# Controller.net
KiCad netlist of a schematic drawn in EAGLE
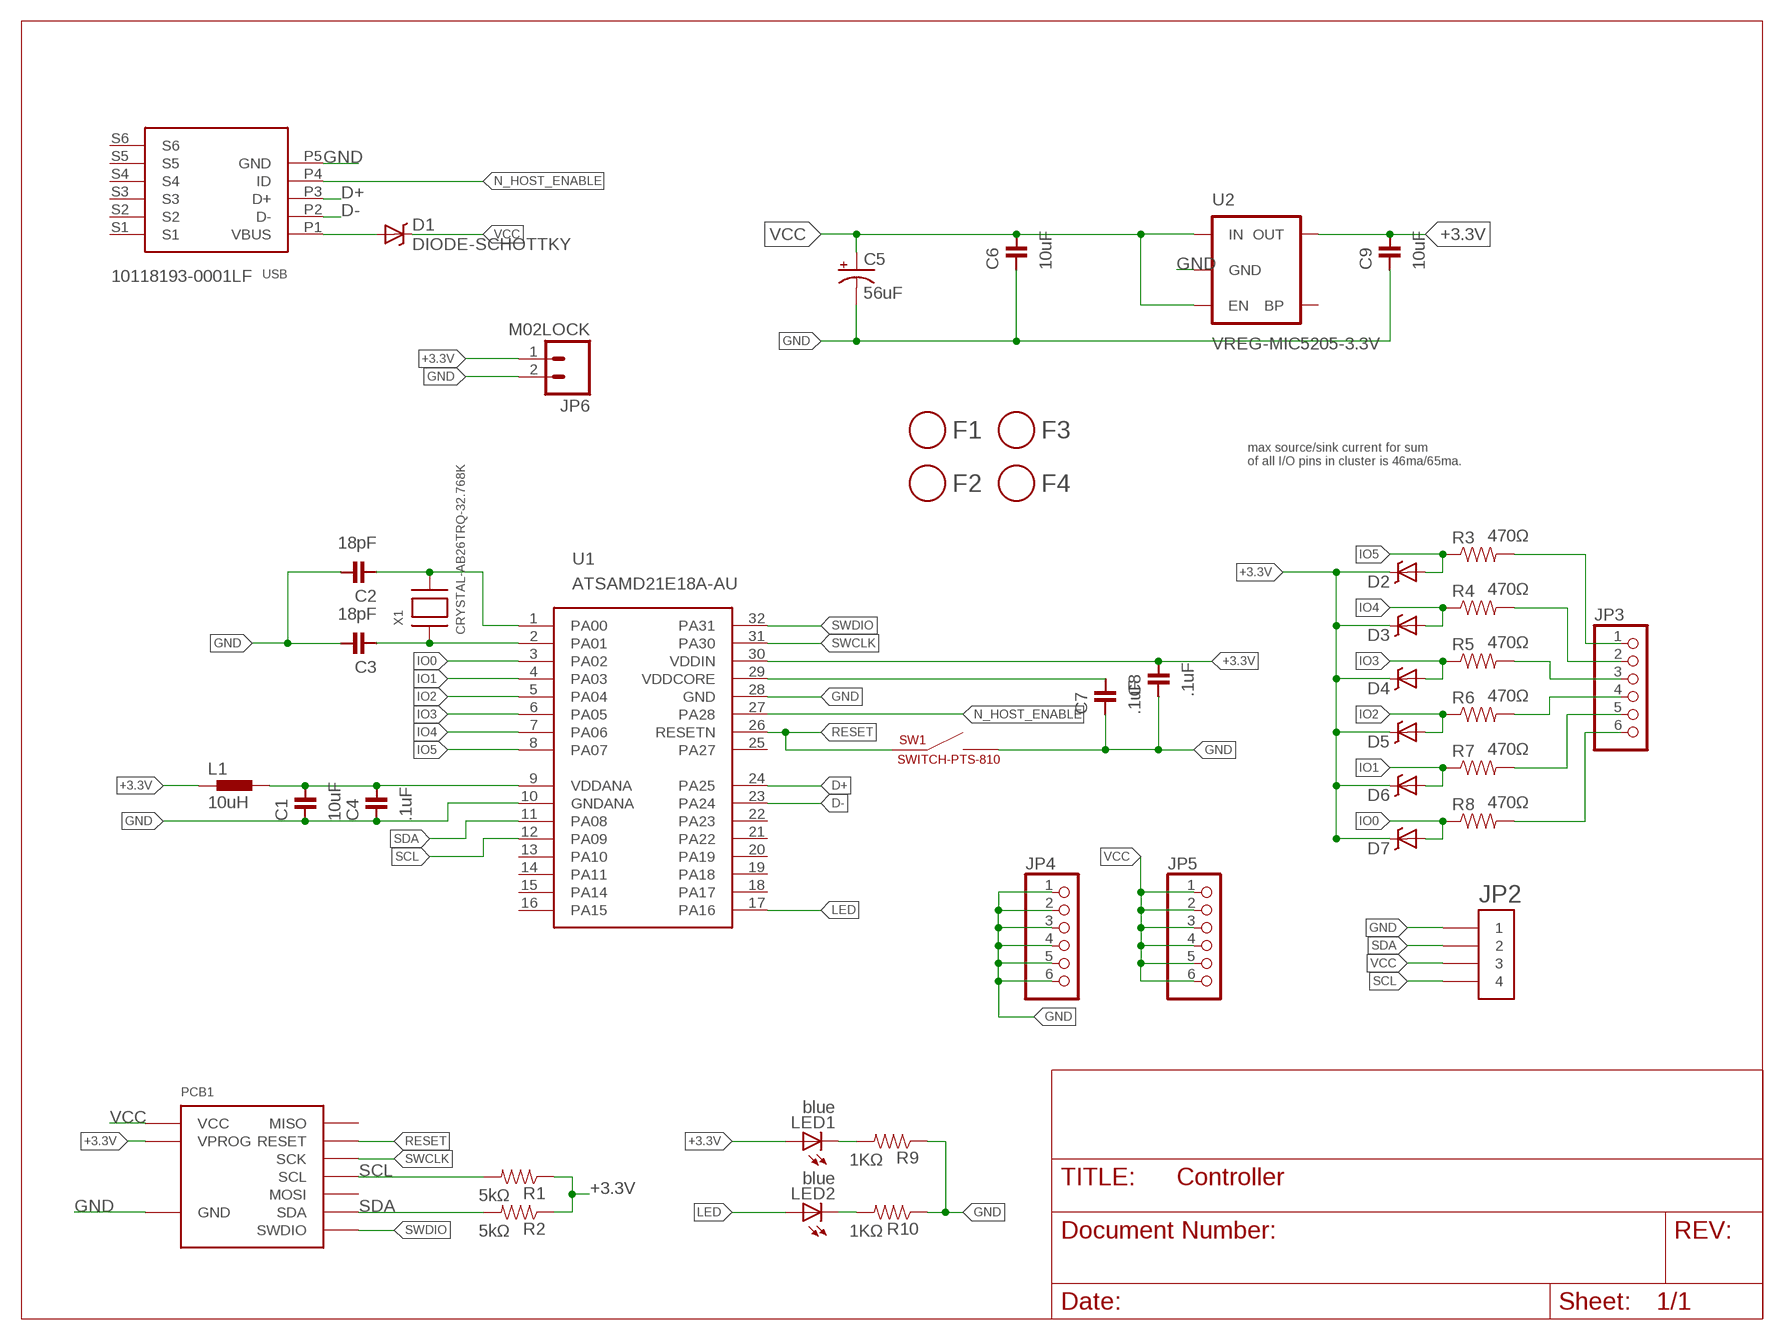
[diagram p0: schematic, sheet 1]

(export (version "E")
  (design (tool "Eeschema 10.0.6"))
  (components
    (comp (ref "C1")
      (value "10uF")
      (footprint "eagle-import:0603")
      (fields (field (name "PARTNUM") "GRM188R61C106MA73D"))
      (libsource (lib "eagle-import") (part "CAPACITOR-10UF"))
    )
    (comp (ref "C2")
      (value "18pF")
      (footprint "eagle-import:0603")
      (fields (field (name "PARTNUM") "C0603C180J5GACTU"))
      (libsource (lib "eagle-import") (part "CAPACITOR-18PF"))
    )
    (comp (ref "C3")
      (value "18pF")
      (footprint "eagle-import:0603")
      (fields (field (name "PARTNUM") "C0603C180J5GACTU"))
      (libsource (lib "eagle-import") (part "CAPACITOR-18PF"))
    )
    (comp (ref "C4")
      (value ".1uF")
      (footprint "eagle-import:0603")
      (fields (field (name "PARTNUM") "C0603C104K5RACTU"))
      (libsource (lib "eagle-import") (part "CAPACITOR-.1UF"))
    )
    (comp (ref "C5")
      (value "56uF")
      (footprint "eagle-import:PANASONIC_D")
      (fields (field (name "PARTNUM") "EMVA250ADA560MF55G"))
      (libsource (lib "eagle-import") (part "CAPACITOR-POL-56UF-25V"))
    )
    (comp (ref "C6")
      (value "10uF")
      (footprint "eagle-import:0603")
      (fields (field (name "PARTNUM") "GRM188R61C106MA73D"))
      (libsource (lib "eagle-import") (part "CAPACITOR-10UF"))
    )
    (comp (ref "C7")
      (value ".1uF")
      (footprint "eagle-import:0603")
      (fields (field (name "PARTNUM") "C0603C104K5RACTU"))
      (libsource (lib "eagle-import") (part "CAPACITOR-.1UF"))
    )
    (comp (ref "C8")
      (value ".1uF")
      (footprint "eagle-import:0603")
      (fields (field (name "PARTNUM") "C0603C104K5RACTU"))
      (libsource (lib "eagle-import") (part "CAPACITOR-.1UF"))
    )
    (comp (ref "C9")
      (value "10uF")
      (footprint "eagle-import:0603")
      (fields (field (name "PARTNUM") "GRM188R61C106MA73D"))
      (libsource (lib "eagle-import") (part "CAPACITOR-10UF"))
    )
    (comp (ref "D1")
      (value "DIODE-SCHOTTKY")
      (footprint "eagle-import:SMP")
      (fields (field (name "PARTNUM") "SS3P3-M3/84A"))
      (libsource (lib "eagle-import") (part "DIODE-SCHOTTKY"))
    )
    (comp (ref "D2")
      (value "DIODE-SCHOTTKY-BAT60A")
      (footprint "eagle-import:SOD-323")
      (fields (field (name "PARTNUM") "BAT60A") (field (name "PARTNUM_1") "RB751V40"))
      (libsource (lib "eagle-import") (part "DIODE-SCHOTTKY-BAT60A"))
    )
    (comp (ref "D3")
      (value "DIODE-SCHOTTKY-BAT60A")
      (footprint "eagle-import:SOD-323")
      (fields (field (name "PARTNUM") "BAT60A") (field (name "PARTNUM_1") "RB751V40"))
      (libsource (lib "eagle-import") (part "DIODE-SCHOTTKY-BAT60A"))
    )
    (comp (ref "D4")
      (value "DIODE-SCHOTTKY-BAT60A")
      (footprint "eagle-import:SOD-323")
      (fields (field (name "PARTNUM") "BAT60A") (field (name "PARTNUM_1") "RB751V40"))
      (libsource (lib "eagle-import") (part "DIODE-SCHOTTKY-BAT60A"))
    )
    (comp (ref "D5")
      (value "DIODE-SCHOTTKY-BAT60A")
      (footprint "eagle-import:SOD-323")
      (fields (field (name "PARTNUM") "BAT60A") (field (name "PARTNUM_1") "RB751V40"))
      (libsource (lib "eagle-import") (part "DIODE-SCHOTTKY-BAT60A"))
    )
    (comp (ref "D6")
      (value "DIODE-SCHOTTKY-BAT60A")
      (footprint "eagle-import:SOD-323")
      (fields (field (name "PARTNUM") "BAT60A") (field (name "PARTNUM_1") "RB751V40"))
      (libsource (lib "eagle-import") (part "DIODE-SCHOTTKY-BAT60A"))
    )
    (comp (ref "D7")
      (value "DIODE-SCHOTTKY-BAT60A")
      (footprint "eagle-import:SOD-323")
      (fields (field (name "PARTNUM") "BAT60A") (field (name "PARTNUM_1") "RB751V40"))
      (libsource (lib "eagle-import") (part "DIODE-SCHOTTKY-BAT60A"))
    )
    (comp (ref "F1")
      (value "FIDUCIAL")
      (footprint "eagle-import:FIDUCIAL_1MM")
      (libsource (lib "eagle-import") (part "FIDUCIAL"))
    )
    (comp (ref "F2")
      (value "FIDUCIAL")
      (footprint "eagle-import:FIDUCIAL_1MM")
      (libsource (lib "eagle-import") (part "FIDUCIAL"))
    )
    (comp (ref "F3")
      (value "FIDUCIAL")
      (footprint "eagle-import:FIDUCIAL_1MM")
      (libsource (lib "eagle-import") (part "FIDUCIAL"))
    )
    (comp (ref "F4")
      (value "FIDUCIAL")
      (footprint "eagle-import:FIDUCIAL_1MM")
      (libsource (lib "eagle-import") (part "FIDUCIAL"))
    )
    (comp (ref "JP1")
      (value "USBFCI-MICROB")
      (footprint "eagle-import:USB-MICROB-FCI")
      (fields (field (name "PARTNUM") "10118193-0001LF"))
      (libsource (lib "eagle-import") (part "USBFCI-MICROB"))
    )
    (comp (ref "JP2")
      (value "HEADER-1X4-AMPMODU")
      (footprint "eagle-import:AMPMODU-4P")
      (fields (field (name "PARTNUM") "147721-3"))
      (libsource (lib "eagle-import") (part "HEADER-1X4-AMPMODU"))
    )
    (comp (ref "JP3")
      (value "PINHD-1X6LOCK")
      (footprint "eagle-import:1X06-BIGLOCK")
      (fields (field (name "PARTNUM") "M20-9990646"))
      (libsource (lib "eagle-import") (part "PINHD-1X6LOCK"))
    )
    (comp (ref "JP4")
      (value "PINHD-1X6LOCK")
      (footprint "eagle-import:1X06-BIGLOCK")
      (fields (field (name "PARTNUM") "M20-9990646"))
      (libsource (lib "eagle-import") (part "PINHD-1X6LOCK"))
    )
    (comp (ref "JP5")
      (value "PINHD-1X6LOCK")
      (footprint "eagle-import:1X06-BIGLOCK")
      (fields (field (name "PARTNUM") "M20-9990646"))
      (libsource (lib "eagle-import") (part "PINHD-1X6LOCK"))
    )
    (comp (ref "JP6")
      (value "M02LOCK")
      (footprint "eagle-import:1X02_LOCK")
      (fields (field (name "PARTNUM") "M20-9990246"))
      (libsource (lib "eagle-import") (part "M02LOCK"))
    )
    (comp (ref "L1")
      (value "10uH")
      (footprint "eagle-import:0603")
      (fields (field (name "PARTNUM") "LQM18FN100M00D") (field (name "PARTNUM_1") "BLM18TG102TN1D"))
      (libsource (lib "eagle-import") (part "INDUCTOR-10UH"))
    )
    (comp (ref "LED1")
      (value "blue")
      (footprint "eagle-import:0805-LED")
      (fields (field (name "PARTNUM") "LTST-C171TBKT") (field (name "PARTNUM_1") "LTST-C171KRKT"))
      (libsource (lib "eagle-import") (part "LED-0805-BLUE"))
    )
    (comp (ref "LED2")
      (value "blue")
      (footprint "eagle-import:0805-LED")
      (fields (field (name "PARTNUM") "LTST-C171TBKT"))
      (libsource (lib "eagle-import") (part "LED-0805-BLUE"))
    )
    (comp (ref "PCB1")
      (value "DEVICE-PCB")
      (footprint "eagle-import:DEVICE-PCB")
      (fields (field (name "PARTNUM") "Controller PCB"))
      (libsource (lib "eagle-import") (part "DEVICE-PCB"))
    )
    (comp (ref "R1")
      (value "5kΩ")
      (footprint "eagle-import:0603")
      (fields (field (name "PARTNUM") "ERJ-3EKF5101V"))
      (libsource (lib "eagle-import") (part "RESISTOR-5KΩ"))
    )
    (comp (ref "R2")
      (value "5kΩ")
      (footprint "eagle-import:0603")
      (fields (field (name "PARTNUM") "ERJ-3EKF5101V"))
      (libsource (lib "eagle-import") (part "RESISTOR-5KΩ"))
    )
    (comp (ref "R3")
      (value "470Ω")
      (footprint "eagle-import:0603")
      (fields (field (name "PARTNUM") "ERJ-3EKF4700V"))
      (libsource (lib "eagle-import") (part "RESISTOR-470Ω"))
    )
    (comp (ref "R4")
      (value "470Ω")
      (footprint "eagle-import:0603")
      (fields (field (name "PARTNUM") "ERJ-3EKF4700V"))
      (libsource (lib "eagle-import") (part "RESISTOR-470Ω"))
    )
    (comp (ref "R5")
      (value "470Ω")
      (footprint "eagle-import:0603")
      (fields (field (name "PARTNUM") "ERJ-3EKF4700V"))
      (libsource (lib "eagle-import") (part "RESISTOR-470Ω"))
    )
    (comp (ref "R6")
      (value "470Ω")
      (footprint "eagle-import:0603")
      (fields (field (name "PARTNUM") "ERJ-3EKF4700V"))
      (libsource (lib "eagle-import") (part "RESISTOR-470Ω"))
    )
    (comp (ref "R7")
      (value "470Ω")
      (footprint "eagle-import:0603")
      (fields (field (name "PARTNUM") "ERJ-3EKF4700V"))
      (libsource (lib "eagle-import") (part "RESISTOR-470Ω"))
    )
    (comp (ref "R8")
      (value "470Ω")
      (footprint "eagle-import:0603")
      (fields (field (name "PARTNUM") "ERJ-3EKF4700V"))
      (libsource (lib "eagle-import") (part "RESISTOR-470Ω"))
    )
    (comp (ref "R9")
      (value "1KΩ")
      (footprint "eagle-import:0603")
      (fields (field (name "PARTNUM") "ERJ-3EKF1001V"))
      (libsource (lib "eagle-import") (part "RESISTOR-1KΩ"))
    )
    (comp (ref "R10")
      (value "1KΩ")
      (footprint "eagle-import:0603")
      (fields (field (name "PARTNUM") "ERJ-3EKF1001V"))
      (libsource (lib "eagle-import") (part "RESISTOR-1KΩ"))
    )
    (comp (ref "SW1")
      (value "SWITCH-PTS-810")
      (footprint "eagle-import:TACT-SWITCH-PTS-810")
      (fields (field (name "PARTNUM") "PTS810 SJM 250 SMTR LFS"))
      (libsource (lib "eagle-import") (part "SWITCH-PTS-810"))
    )
    (comp (ref "U1")
      (value "ATSAMD21E18A-AU")
      (footprint "eagle-import:TQFP-32")
      (fields (field (name "PARTNUM") "ATSAMD21E18A-AUT"))
      (libsource (lib "eagle-import") (part "SAMD21E"))
    )
    (comp (ref "U2")
      (value "VREG-MIC5205-3.3V")
      (footprint "eagle-import:SOT23-5")
      (fields (field (name "PARTNUM") "MIC5205-3.3YM5 TR") (field (name "PARTNUM_1") "MIC5205-3.3YM5 TR"))
      (libsource (lib "eagle-import") (part "VREG-MIC5205-3.3V"))
    )
    (comp (ref "X1")
      (value "CRYSTAL-AB26TRQ-32.768K")
      (footprint "eagle-import:CRYSTAL-AB26TRQ")
      (fields (field (name "PARTNUM") "AB26TRQ-32.768KHZ-T"))
      (libsource (lib "eagle-import") (part "CRYSTAL-AB26TRQ-32.768K"))
    )
  )
  (nets
    (net (code "1") (name "+3.3V") (class "Default")
      (node (ref "C8") (pin "1") (pinfunction "1_1") (pintype "passive"))
      (node (ref "C9") (pin "1") (pinfunction "1_1") (pintype "passive"))
      (node (ref "D2") (pin "C") (pinfunction "C_C") (pintype "passive"))
      (node (ref "D3") (pin "C") (pinfunction "C_C") (pintype "passive"))
      (node (ref "D4") (pin "C") (pinfunction "C_C") (pintype "passive"))
      (node (ref "D5") (pin "C") (pinfunction "C_C") (pintype "passive"))
      (node (ref "D6") (pin "C") (pinfunction "C_C") (pintype "passive"))
      (node (ref "D7") (pin "C") (pinfunction "C_C") (pintype "passive"))
      (node (ref "JP6") (pin "1") (pinfunction "1_1") (pintype "passive"))
      (node (ref "L1") (pin "1") (pinfunction "1_1") (pintype "passive"))
      (node (ref "LED1") (pin "A") (pinfunction "A_A") (pintype "passive"))
      (node (ref "PCB1") (pin "VPROG") (pinfunction "VPROG_VPROG") (pintype "bidirectional"))
      (node (ref "R1") (pin "1") (pinfunction "1_1") (pintype "passive"))
      (node (ref "R2") (pin "1") (pinfunction "1_1") (pintype "passive"))
      (node (ref "U1") (pin "30") (pinfunction "VDDIN_30") (pintype "bidirectional"))
      (node (ref "U2") (pin "5") (pinfunction "OUT_5") (pintype "passive"))
    )
    (net (code "2") (name "D+") (class "Default")
      (node (ref "JP1") (pin "P3") (pinfunction "D+_P3") (pintype "bidirectional"))
      (node (ref "U1") (pin "24") (pinfunction "PA25_24") (pintype "bidirectional"))
    )
    (net (code "3") (name "D-") (class "Default")
      (node (ref "JP1") (pin "P2") (pinfunction "D-_P2") (pintype "bidirectional"))
      (node (ref "U1") (pin "23") (pinfunction "PA24_23") (pintype "bidirectional"))
    )
    (net (code "4") (name "GND") (class "Default")
      (node (ref "C1") (pin "2") (pinfunction "2_2") (pintype "passive"))
      (node (ref "C2") (pin "1") (pinfunction "1_1") (pintype "passive"))
      (node (ref "C3") (pin "1") (pinfunction "1_1") (pintype "passive"))
      (node (ref "C4") (pin "2") (pinfunction "2_2") (pintype "passive"))
      (node (ref "C5") (pin "-") (pinfunction "-_-") (pintype "passive"))
      (node (ref "C6") (pin "2") (pinfunction "2_2") (pintype "passive"))
      (node (ref "C7") (pin "2") (pinfunction "2_2") (pintype "passive"))
      (node (ref "C8") (pin "2") (pinfunction "2_2") (pintype "passive"))
      (node (ref "C9") (pin "2") (pinfunction "2_2") (pintype "passive"))
      (node (ref "JP1") (pin "P5") (pinfunction "GND_P5") (pintype "bidirectional"))
      (node (ref "JP2") (pin "P$1") (pinfunction "1_P$1") (pintype "bidirectional"))
      (node (ref "JP2") (pin "P$2") (pinfunction "1_P$2") (pintype "bidirectional"))
      (node (ref "JP4") (pin "1") (pinfunction "1_1") (pintype "passive"))
      (node (ref "JP4") (pin "2") (pinfunction "2_2") (pintype "passive"))
      (node (ref "JP4") (pin "3") (pinfunction "3_3") (pintype "passive"))
      (node (ref "JP4") (pin "4") (pinfunction "4_4") (pintype "passive"))
      (node (ref "JP4") (pin "5") (pinfunction "5_5") (pintype "passive"))
      (node (ref "JP4") (pin "6") (pinfunction "6_6") (pintype "passive"))
      (node (ref "JP6") (pin "2") (pinfunction "2_2") (pintype "passive"))
      (node (ref "PCB1") (pin "GND") (pinfunction "GND_GND") (pintype "bidirectional"))
      (node (ref "R10") (pin "1") (pinfunction "1_1") (pintype "passive"))
      (node (ref "R9") (pin "1") (pinfunction "1_1") (pintype "passive"))
      (node (ref "SW1") (pin "P$3") (pinfunction "NEG1_P$3") (pintype "bidirectional"))
      (node (ref "SW1") (pin "P$4") (pinfunction "NEG1_P$4") (pintype "bidirectional"))
      (node (ref "U1") (pin "10") (pinfunction "GNDANA_10") (pintype "bidirectional"))
      (node (ref "U1") (pin "28") (pinfunction "GND_28") (pintype "bidirectional"))
      (node (ref "U2") (pin "2") (pinfunction "GND_2") (pintype "input"))
    )
    (net (code "5") (name "IO0") (class "Default")
      (node (ref "D7") (pin "A") (pinfunction "A_A") (pintype "passive"))
      (node (ref "R8") (pin "1") (pinfunction "1_1") (pintype "passive"))
      (node (ref "U1") (pin "3") (pinfunction "PA02_3") (pintype "bidirectional"))
    )
    (net (code "6") (name "IO1") (class "Default")
      (node (ref "D6") (pin "A") (pinfunction "A_A") (pintype "passive"))
      (node (ref "R7") (pin "1") (pinfunction "1_1") (pintype "passive"))
      (node (ref "U1") (pin "4") (pinfunction "PA03_4") (pintype "bidirectional"))
    )
    (net (code "7") (name "IO2") (class "Default")
      (node (ref "D5") (pin "A") (pinfunction "A_A") (pintype "passive"))
      (node (ref "R6") (pin "1") (pinfunction "1_1") (pintype "passive"))
      (node (ref "U1") (pin "5") (pinfunction "PA04_5") (pintype "bidirectional"))
    )
    (net (code "8") (name "IO3") (class "Default")
      (node (ref "D4") (pin "A") (pinfunction "A_A") (pintype "passive"))
      (node (ref "R5") (pin "1") (pinfunction "1_1") (pintype "passive"))
      (node (ref "U1") (pin "6") (pinfunction "PA05_6") (pintype "bidirectional"))
    )
    (net (code "9") (name "IO4") (class "Default")
      (node (ref "D3") (pin "A") (pinfunction "A_A") (pintype "passive"))
      (node (ref "R4") (pin "1") (pinfunction "1_1") (pintype "passive"))
      (node (ref "U1") (pin "7") (pinfunction "PA06_7") (pintype "bidirectional"))
    )
    (net (code "10") (name "IO5") (class "Default")
      (node (ref "D2") (pin "A") (pinfunction "A_A") (pintype "passive"))
      (node (ref "R3") (pin "1") (pinfunction "1_1") (pintype "passive"))
      (node (ref "U1") (pin "8") (pinfunction "PA07_8") (pintype "bidirectional"))
    )
    (net (code "11") (name "LED") (class "Default")
      (node (ref "LED2") (pin "A") (pinfunction "A_A") (pintype "passive"))
      (node (ref "U1") (pin "17") (pinfunction "PA16_17") (pintype "bidirectional"))
    )
    (net (code "12") (name "N_HOST_ENABLE") (class "Default")
      (node (ref "JP1") (pin "P4") (pinfunction "ID_P4") (pintype "bidirectional"))
      (node (ref "U1") (pin "27") (pinfunction "PA28_27") (pintype "bidirectional"))
    )
    (net (code "13") (name "Net-(JP1-VBUS)") (class "Default")
      (node (ref "D1") (pin "A") (pinfunction "A_A") (pintype "passive"))
      (node (ref "JP1") (pin "P1") (pinfunction "VBUS_P1") (pintype "bidirectional"))
    )
    (net (code "14") (name "Net-(JP3-Pad1)") (class "Default")
      (node (ref "JP3") (pin "1") (pinfunction "1_1") (pintype "passive"))
      (node (ref "R3") (pin "2") (pinfunction "2_2") (pintype "passive"))
    )
    (net (code "15") (name "Net-(JP3-Pad2)") (class "Default")
      (node (ref "JP3") (pin "2") (pinfunction "2_2") (pintype "passive"))
      (node (ref "R4") (pin "2") (pinfunction "2_2") (pintype "passive"))
    )
    (net (code "16") (name "Net-(JP3-Pad3)") (class "Default")
      (node (ref "JP3") (pin "3") (pinfunction "3_3") (pintype "passive"))
      (node (ref "R5") (pin "2") (pinfunction "2_2") (pintype "passive"))
    )
    (net (code "17") (name "Net-(JP3-Pad4)") (class "Default")
      (node (ref "JP3") (pin "4") (pinfunction "4_4") (pintype "passive"))
      (node (ref "R6") (pin "2") (pinfunction "2_2") (pintype "passive"))
    )
    (net (code "18") (name "Net-(JP3-Pad5)") (class "Default")
      (node (ref "JP3") (pin "5") (pinfunction "5_5") (pintype "passive"))
      (node (ref "R7") (pin "2") (pinfunction "2_2") (pintype "passive"))
    )
    (net (code "19") (name "Net-(JP3-Pad6)") (class "Default")
      (node (ref "JP3") (pin "6") (pinfunction "6_6") (pintype "passive"))
      (node (ref "R8") (pin "2") (pinfunction "2_2") (pintype "passive"))
    )
    (net (code "20") (name "Net-(LED1-PadC)") (class "Default")
      (node (ref "LED1") (pin "C") (pinfunction "C_C") (pintype "passive"))
      (node (ref "R9") (pin "2") (pinfunction "2_2") (pintype "passive"))
    )
    (net (code "21") (name "Net-(LED2-PadC)") (class "Default")
      (node (ref "LED2") (pin "C") (pinfunction "C_C") (pintype "passive"))
      (node (ref "R10") (pin "2") (pinfunction "2_2") (pintype "passive"))
    )
    (net (code "22") (name "Net-(U1-PA00)") (class "Default")
      (node (ref "C2") (pin "2") (pinfunction "2_2") (pintype "passive"))
      (node (ref "U1") (pin "1") (pinfunction "PA00_1") (pintype "bidirectional"))
      (node (ref "X1") (pin "XOUT") (pinfunction "X2_XOUT") (pintype "bidirectional"))
    )
    (net (code "23") (name "Net-(U1-PA01)") (class "Default")
      (node (ref "C3") (pin "2") (pinfunction "2_2") (pintype "passive"))
      (node (ref "U1") (pin "2") (pinfunction "PA01_2") (pintype "bidirectional"))
      (node (ref "X1") (pin "XIN") (pinfunction "X1_XIN") (pintype "bidirectional"))
    )
    (net (code "24") (name "Net-(U1-VDDANA)") (class "Default")
      (node (ref "C1") (pin "1") (pinfunction "1_1") (pintype "passive"))
      (node (ref "C4") (pin "1") (pinfunction "1_1") (pintype "passive"))
      (node (ref "L1") (pin "2") (pinfunction "2_2") (pintype "passive"))
      (node (ref "U1") (pin "9") (pinfunction "VDDANA_9") (pintype "bidirectional"))
    )
    (net (code "25") (name "Net-(U1-VDDCORE)") (class "Default")
      (node (ref "C7") (pin "1") (pinfunction "1_1") (pintype "passive"))
      (node (ref "U1") (pin "29") (pinfunction "VDDCORE_29") (pintype "bidirectional"))
    )
    (net (code "26") (name "RESET") (class "Default")
      (node (ref "PCB1") (pin "RESET") (pinfunction "RESET_RESET") (pintype "bidirectional"))
      (node (ref "SW1") (pin "P$1") (pinfunction "POS1_P$1") (pintype "bidirectional"))
      (node (ref "SW1") (pin "P$2") (pinfunction "POS1_P$2") (pintype "bidirectional"))
      (node (ref "U1") (pin "26") (pinfunction "RESETN_26") (pintype "bidirectional"))
    )
    (net (code "27") (name "SCL") (class "Default")
      (node (ref "JP2") (pin "P$7") (pinfunction "4_P$7") (pintype "bidirectional"))
      (node (ref "JP2") (pin "P$8") (pinfunction "4_P$8") (pintype "bidirectional"))
      (node (ref "PCB1") (pin "SCL") (pinfunction "SCL_SCL") (pintype "bidirectional"))
      (node (ref "R1") (pin "2") (pinfunction "2_2") (pintype "passive"))
      (node (ref "U1") (pin "12") (pinfunction "PA09_12") (pintype "bidirectional"))
    )
    (net (code "28") (name "SDA") (class "Default")
      (node (ref "JP2") (pin "P$3") (pinfunction "2_P$3") (pintype "bidirectional"))
      (node (ref "JP2") (pin "P$4") (pinfunction "2_P$4") (pintype "bidirectional"))
      (node (ref "PCB1") (pin "SDA") (pinfunction "SDA_SDA") (pintype "bidirectional"))
      (node (ref "R2") (pin "2") (pinfunction "2_2") (pintype "passive"))
      (node (ref "U1") (pin "11") (pinfunction "PA08_11") (pintype "bidirectional"))
    )
    (net (code "29") (name "SWCLK") (class "Default")
      (node (ref "PCB1") (pin "CLK") (pinfunction "SCK_CLK") (pintype "bidirectional"))
      (node (ref "U1") (pin "31") (pinfunction "PA30_31") (pintype "bidirectional"))
    )
    (net (code "30") (name "SWDIO") (class "Default")
      (node (ref "PCB1") (pin "SWDIO") (pinfunction "SWDIO_SWDIO") (pintype "bidirectional"))
      (node (ref "U1") (pin "32") (pinfunction "PA31_32") (pintype "bidirectional"))
    )
    (net (code "31") (name "VCC") (class "Default")
      (node (ref "C5") (pin "+") (pinfunction "+_+") (pintype "passive"))
      (node (ref "C6") (pin "1") (pinfunction "1_1") (pintype "passive"))
      (node (ref "D1") (pin "C") (pinfunction "C_C") (pintype "passive"))
      (node (ref "JP2") (pin "P$5") (pinfunction "3_P$5") (pintype "bidirectional"))
      (node (ref "JP2") (pin "P$6") (pinfunction "3_P$6") (pintype "bidirectional"))
      (node (ref "JP5") (pin "1") (pinfunction "1_1") (pintype "passive"))
      (node (ref "JP5") (pin "2") (pinfunction "2_2") (pintype "passive"))
      (node (ref "JP5") (pin "3") (pinfunction "3_3") (pintype "passive"))
      (node (ref "JP5") (pin "4") (pinfunction "4_4") (pintype "passive"))
      (node (ref "JP5") (pin "5") (pinfunction "5_5") (pintype "passive"))
      (node (ref "JP5") (pin "6") (pinfunction "6_6") (pintype "passive"))
      (node (ref "PCB1") (pin "VCC") (pinfunction "VCC_VCC") (pintype "bidirectional"))
      (node (ref "U2") (pin "1") (pinfunction "IN_1") (pintype "input"))
      (node (ref "U2") (pin "3") (pinfunction "EN_3") (pintype "input"))
    )
    (net (code "32") (name "unconnected-(JP1-PadS1)") (class "Default")
      (node (ref "JP1") (pin "S1") (pinfunction "S1_S1") (pintype "bidirectional"))
    )
    (net (code "33") (name "unconnected-(JP1-PadS2)") (class "Default")
      (node (ref "JP1") (pin "S2") (pinfunction "S2_S2") (pintype "bidirectional"))
    )
    (net (code "34") (name "unconnected-(JP1-PadS3)") (class "Default")
      (node (ref "JP1") (pin "S3") (pinfunction "S3_S3") (pintype "bidirectional"))
    )
    (net (code "35") (name "unconnected-(JP1-PadS4)") (class "Default")
      (node (ref "JP1") (pin "S4") (pinfunction "S4_S4") (pintype "bidirectional"))
    )
    (net (code "36") (name "unconnected-(JP1-PadS5)") (class "Default")
      (node (ref "JP1") (pin "S5") (pinfunction "S5_S5") (pintype "bidirectional"))
    )
    (net (code "37") (name "unconnected-(JP1-PadS6)") (class "Default")
      (node (ref "JP1") (pin "S6") (pinfunction "S6_S6") (pintype "bidirectional"))
    )
    (net (code "38") (name "unconnected-(PCB1-PadMISO)") (class "Default")
      (node (ref "PCB1") (pin "MISO") (pinfunction "MISO_MISO") (pintype "bidirectional"))
    )
    (net (code "39") (name "unconnected-(PCB1-PadMOSI)") (class "Default")
      (node (ref "PCB1") (pin "MOSI") (pinfunction "MOSI_MOSI") (pintype "bidirectional"))
    )
    (net (code "40") (name "unconnected-(U1-PA10-Pad13)") (class "Default")
      (node (ref "U1") (pin "13") (pinfunction "PA10_13") (pintype "bidirectional"))
    )
    (net (code "41") (name "unconnected-(U1-PA11-Pad14)") (class "Default")
      (node (ref "U1") (pin "14") (pinfunction "PA11_14") (pintype "bidirectional"))
    )
    (net (code "42") (name "unconnected-(U1-PA14-Pad15)") (class "Default")
      (node (ref "U1") (pin "15") (pinfunction "PA14_15") (pintype "bidirectional"))
    )
    (net (code "43") (name "unconnected-(U1-PA15-Pad16)") (class "Default")
      (node (ref "U1") (pin "16") (pinfunction "PA15_16") (pintype "bidirectional"))
    )
    (net (code "44") (name "unconnected-(U1-PA17-Pad18)") (class "Default")
      (node (ref "U1") (pin "18") (pinfunction "PA17_18") (pintype "bidirectional"))
    )
    (net (code "45") (name "unconnected-(U1-PA18-Pad19)") (class "Default")
      (node (ref "U1") (pin "19") (pinfunction "PA18_19") (pintype "bidirectional"))
    )
    (net (code "46") (name "unconnected-(U1-PA19-Pad20)") (class "Default")
      (node (ref "U1") (pin "20") (pinfunction "PA19_20") (pintype "bidirectional"))
    )
    (net (code "47") (name "unconnected-(U1-PA22-Pad21)") (class "Default")
      (node (ref "U1") (pin "21") (pinfunction "PA22_21") (pintype "bidirectional"))
    )
    (net (code "48") (name "unconnected-(U1-PA23-Pad22)") (class "Default")
      (node (ref "U1") (pin "22") (pinfunction "PA23_22") (pintype "bidirectional"))
    )
    (net (code "49") (name "unconnected-(U1-PA27-Pad25)") (class "Default")
      (node (ref "U1") (pin "25") (pinfunction "PA27_25") (pintype "bidirectional"))
    )
    (net (code "50") (name "unconnected-(U2-BP-Pad4)") (class "Default")
      (node (ref "U2") (pin "4") (pinfunction "BP_4") (pintype "input"))
    )
  )
)
